# MotorDrive_REVB2.net
KiCad netlist of a schematic drawn in EAGLE
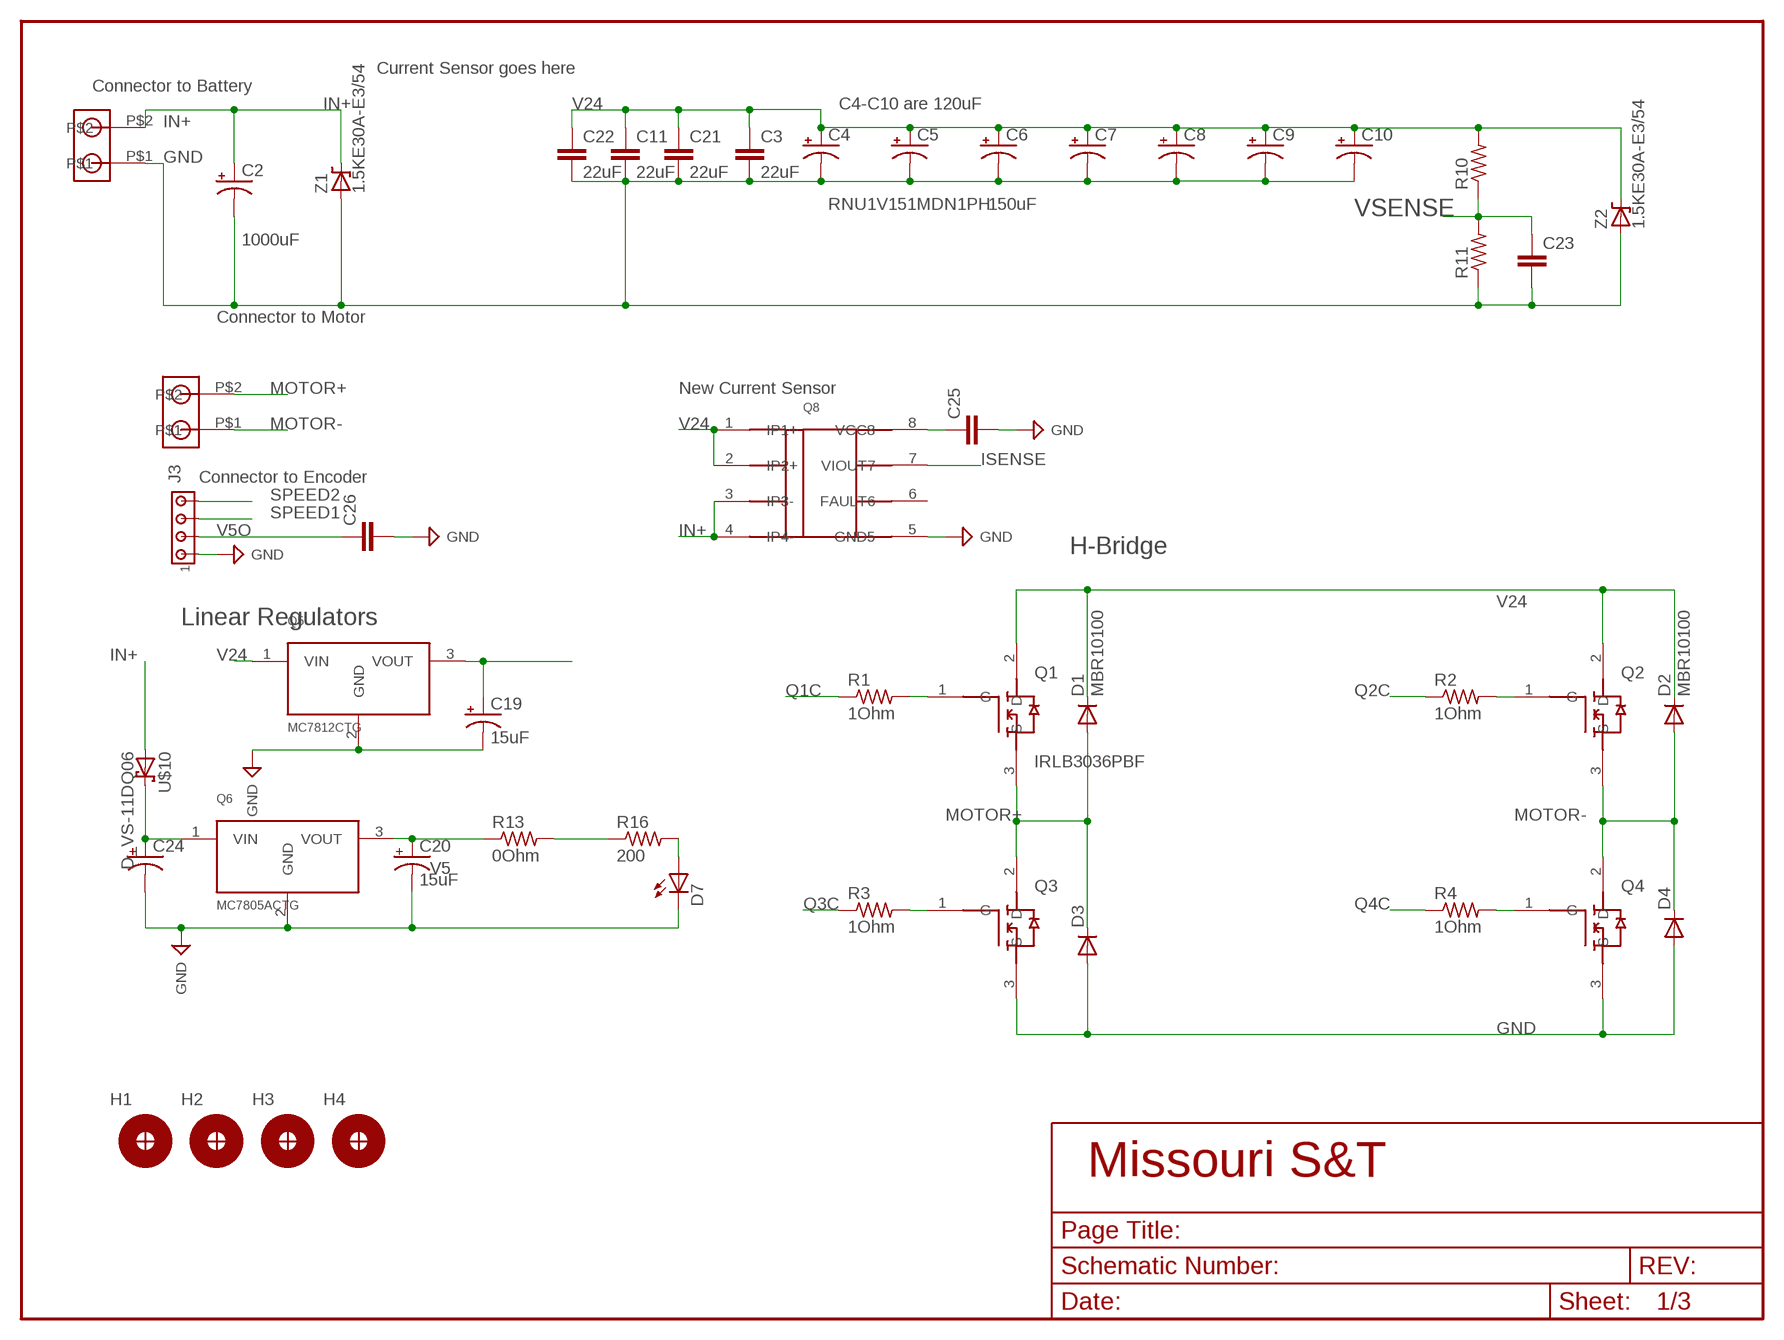
[diagram p0: schematic, sheet 1]
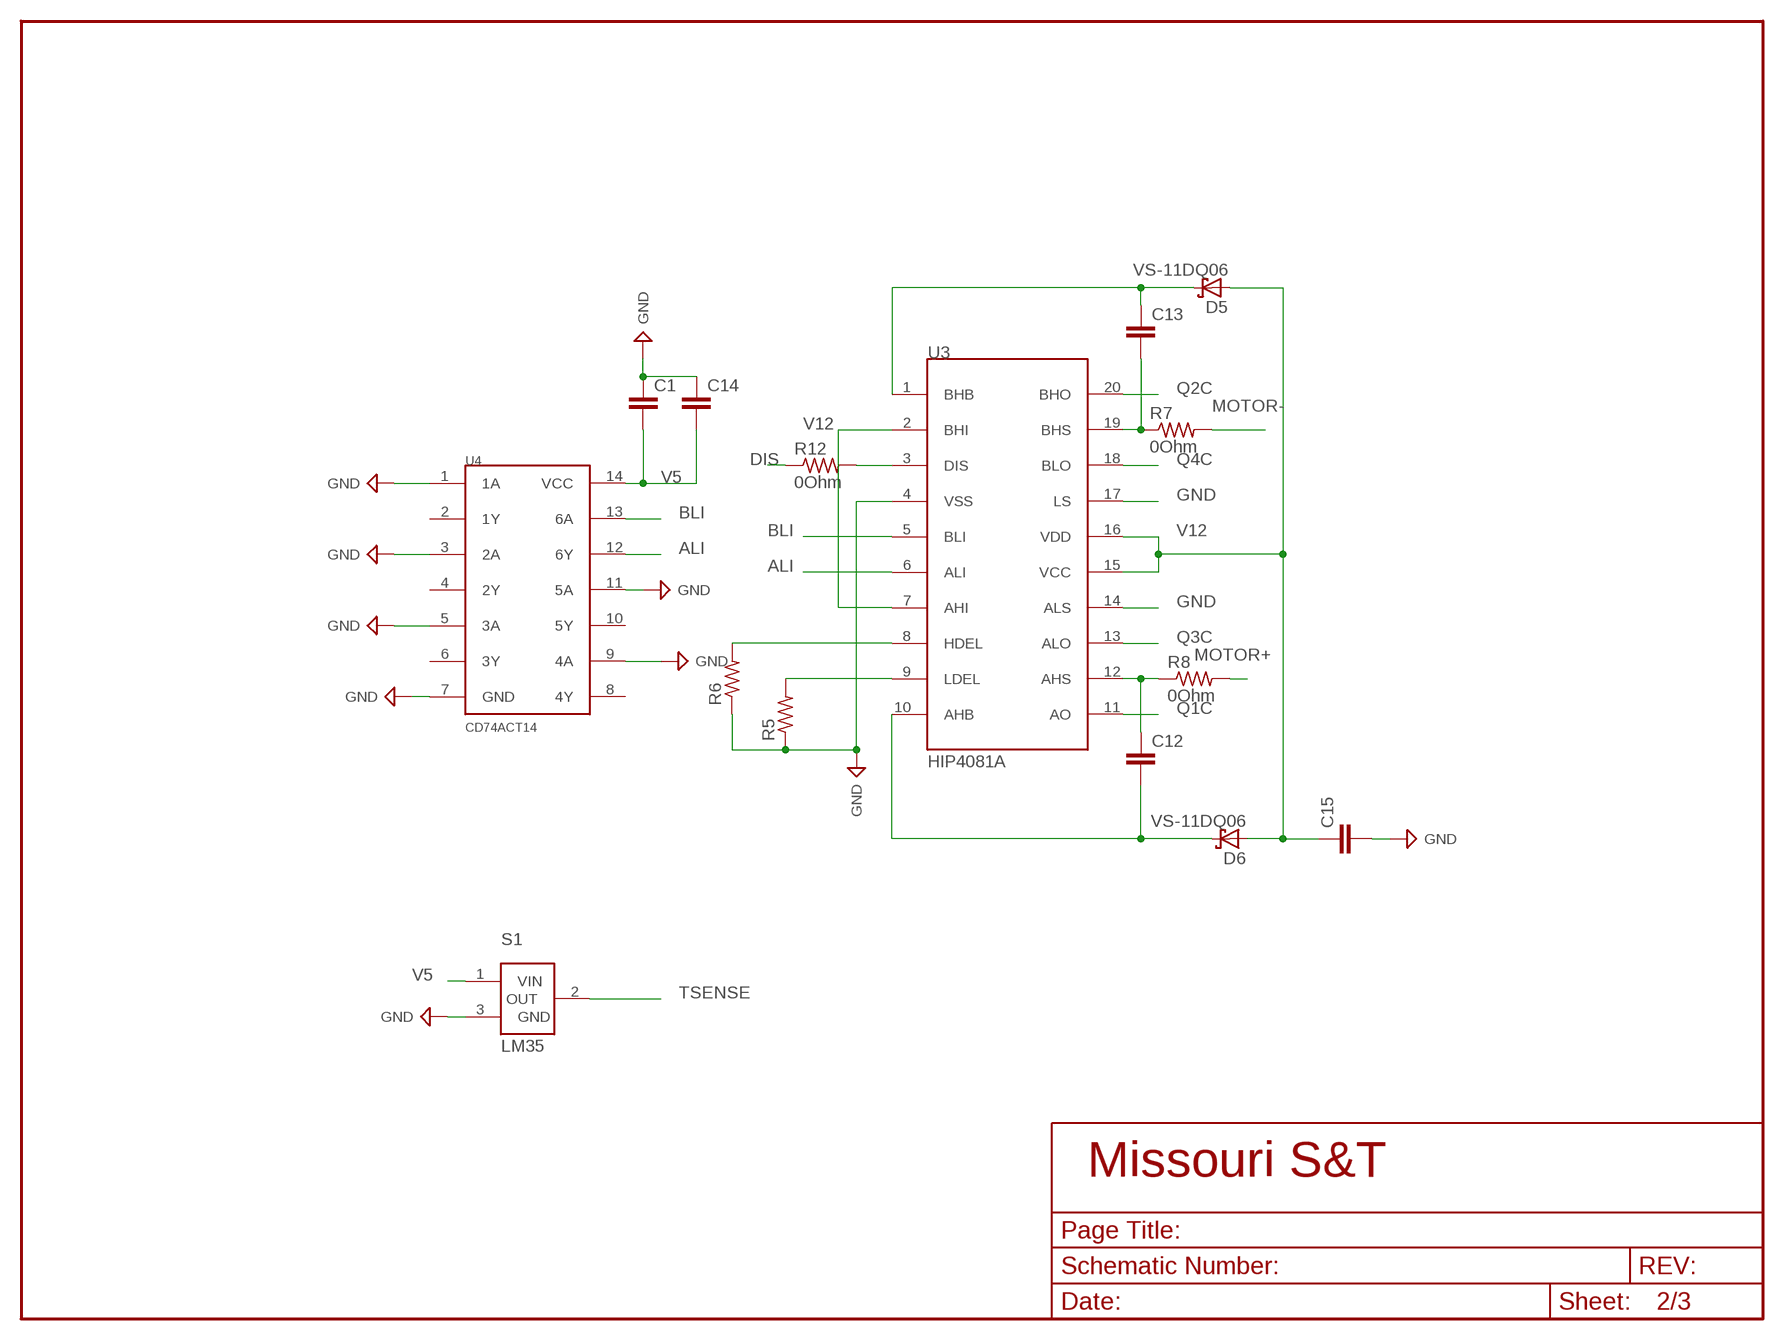
[diagram p1: schematic, sheet 2]
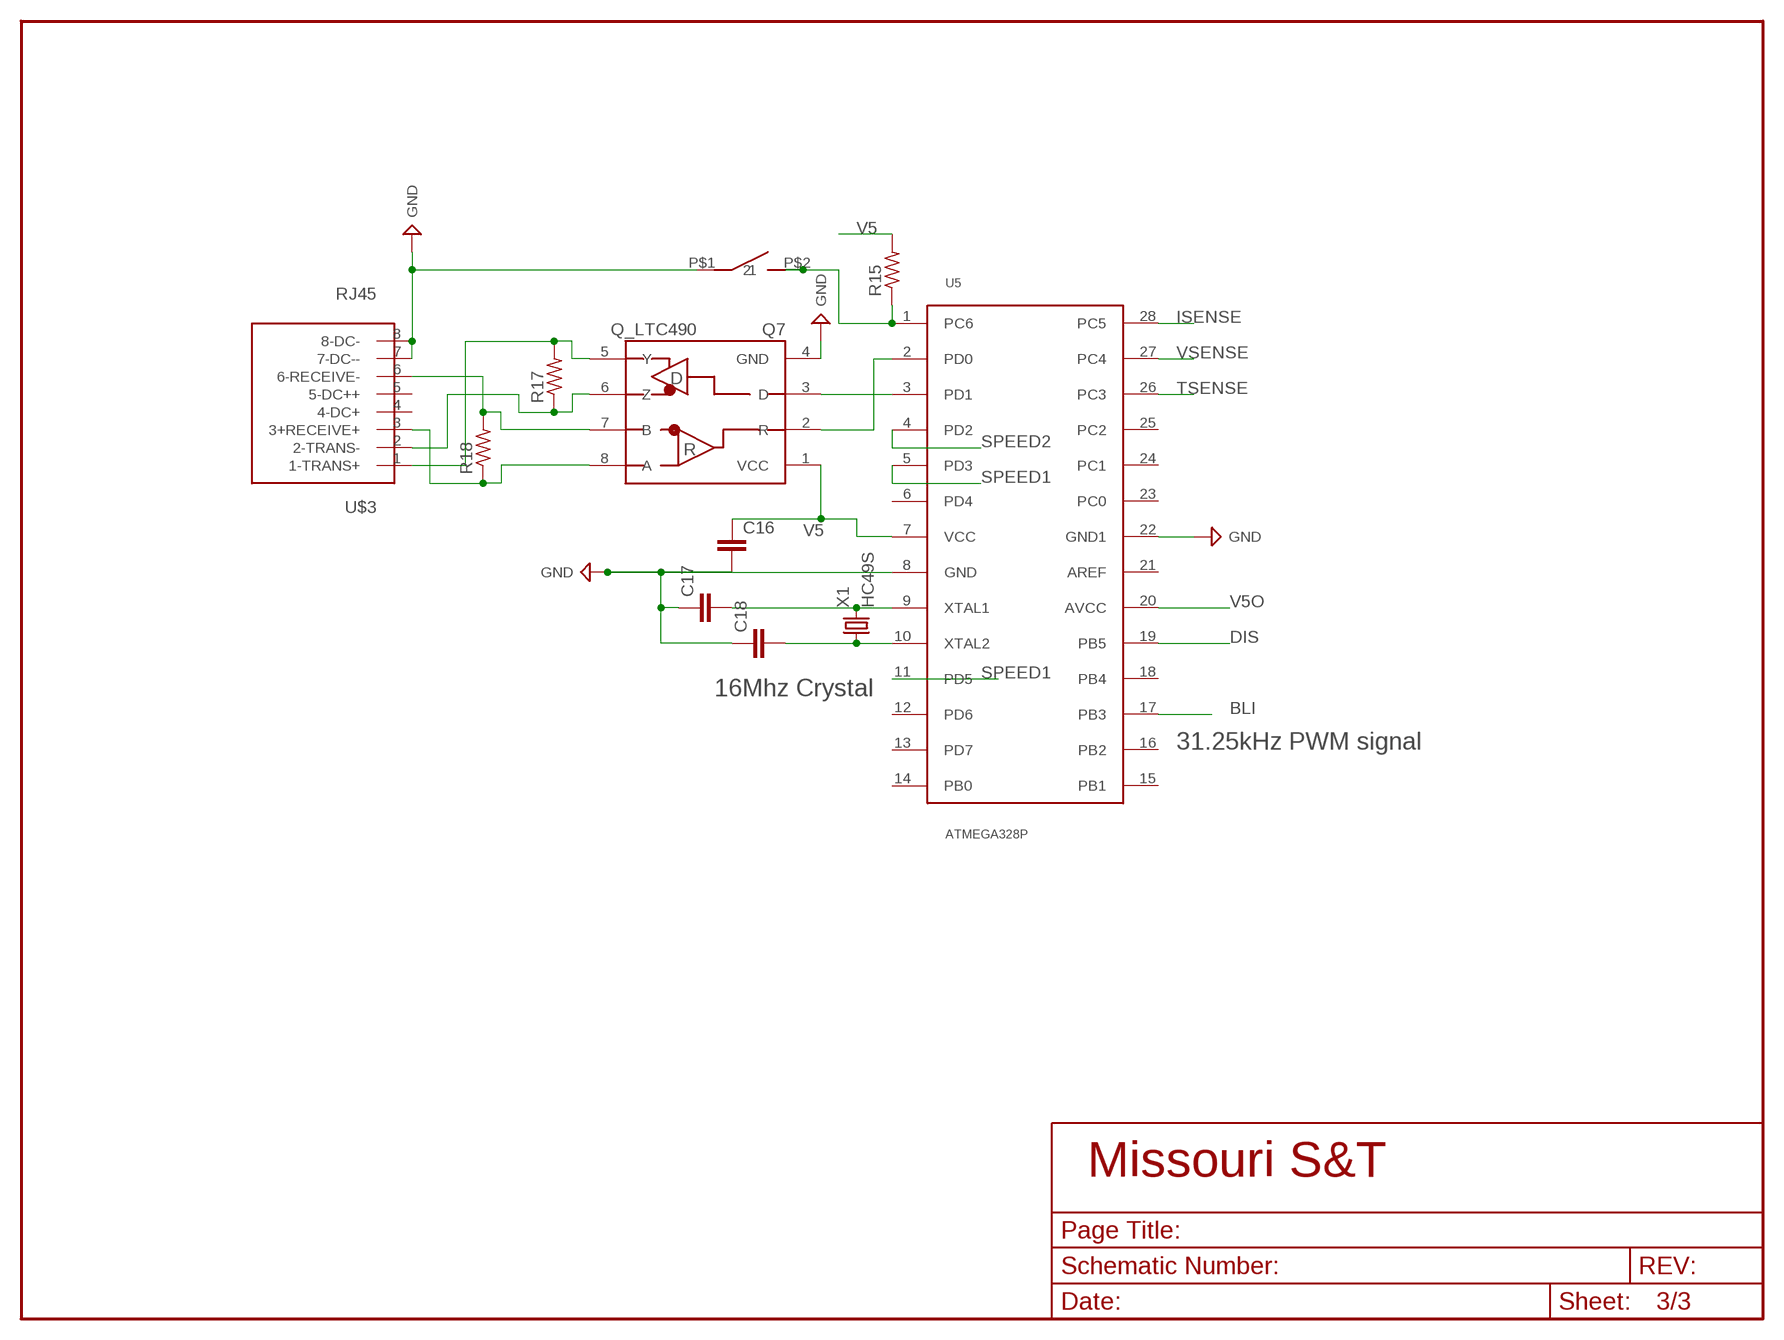
[diagram p2: schematic, sheet 3]

(export (version "E")
  (design (tool "Eeschema 10.0.6"))
  (components
    (comp (ref "C1")
      (value "C_CAP_1206")
      (footprint "eagle-import:C_1206")
      (libsource (lib "eagle-import") (part "C_CAP_1206"))
    )
    (comp (ref "C12")
      (value "C_CAP_1206")
      (footprint "eagle-import:C_1206")
      (libsource (lib "eagle-import") (part "C_CAP_1206"))
    )
    (comp (ref "C13")
      (value "C_CAP_1206")
      (footprint "eagle-import:C_1206")
      (libsource (lib "eagle-import") (part "C_CAP_1206"))
    )
    (comp (ref "C14")
      (value "C_CAP_1206")
      (footprint "eagle-import:C_1206")
      (libsource (lib "eagle-import") (part "C_CAP_1206"))
    )
    (comp (ref "C15")
      (value "C_CAP_1206")
      (footprint "eagle-import:C_1206")
      (libsource (lib "eagle-import") (part "C_CAP_1206"))
    )
    (comp (ref "D5")
      (value "VS-11DQ06")
      (footprint "eagle-import:DO-204AL")
      (libsource (lib "eagle-import") (part "D_VS-11DQ06"))
    )
    (comp (ref "D6")
      (value "VS-11DQ06")
      (footprint "eagle-import:DO-204AL")
      (libsource (lib "eagle-import") (part "D_VS-11DQ06"))
    )
    (comp (ref "R5")
      (value "R_RES_1206")
      (footprint "eagle-import:R_1206")
      (libsource (lib "eagle-import") (part "R_RES_1206"))
    )
    (comp (ref "R6")
      (value "R_RES_1206")
      (footprint "eagle-import:R_1206")
      (libsource (lib "eagle-import") (part "R_RES_1206"))
    )
    (comp (ref "R7")
      (value "0Ohm")
      (footprint "eagle-import:R_1_4W")
      (libsource (lib "eagle-import") (part "R_1/4W"))
    )
    (comp (ref "R8")
      (value "0Ohm")
      (footprint "eagle-import:R_1_4W")
      (libsource (lib "eagle-import") (part "R_1/4W"))
    )
    (comp (ref "R12")
      (value "0Ohm")
      (footprint "eagle-import:R_1_4W")
      (libsource (lib "eagle-import") (part "R_1/4W"))
    )
    (comp (ref "S1")
      (value "LM35")
      (footprint "eagle-import:TO-92-3")
      (libsource (lib "eagle-import") (part "Q_LM35TO-92"))
    )
    (comp (ref "U3")
      (value "HIP4081A")
      (footprint "eagle-import:DIP20")
      (libsource (lib "eagle-import") (part "Q_HIP4081A"))
    )
    (comp (ref "U4")
      (value "CD74ACT14")
      (footprint "eagle-import:DIP14")
      (libsource (lib "eagle-import") (part "Q_CD74ACT14"))
    )
    (comp (ref "C2")
      (value "1000uF")
      (footprint "eagle-import:C_10MM")
      (libsource (lib "eagle-import") (part "C_10MM"))
    )
    (comp (ref "C3")
      (value "22uF")
      (footprint "eagle-import:C_1206")
      (libsource (lib "eagle-import") (part "C_CAP_1206"))
    )
    (comp (ref "C4")
      (value "RNU1V151MDN1PH")
      (footprint "eagle-import:C_10MM")
      (libsource (lib "eagle-import") (part "C_10MM"))
    )
    (comp (ref "C5")
      (value "C_10MM")
      (footprint "eagle-import:C_10MM")
      (libsource (lib "eagle-import") (part "C_10MM"))
    )
    (comp (ref "C6")
      (value "C_10MM")
      (footprint "eagle-import:C_10MM")
      (libsource (lib "eagle-import") (part "C_10MM"))
    )
    (comp (ref "C7")
      (value "C_10MM")
      (footprint "eagle-import:C_10MM")
      (libsource (lib "eagle-import") (part "C_10MM"))
    )
    (comp (ref "C8")
      (value "C_10MM")
      (footprint "eagle-import:C_10MM")
      (libsource (lib "eagle-import") (part "C_10MM"))
    )
    (comp (ref "C9")
      (value "C_10MM")
      (footprint "eagle-import:C_10MM")
      (libsource (lib "eagle-import") (part "C_10MM"))
    )
    (comp (ref "C10")
      (value "150uF")
      (footprint "eagle-import:C_10MM")
      (libsource (lib "eagle-import") (part "C_10MM"))
    )
    (comp (ref "C11")
      (value "22uF")
      (footprint "eagle-import:C_1206")
      (libsource (lib "eagle-import") (part "C_CAP_1206"))
    )
    (comp (ref "C19")
      (value "15uF")
      (footprint "eagle-import:C_2MM")
      (libsource (lib "eagle-import") (part "C_GA1E150"))
    )
    (comp (ref "C20")
      (value "15uF")
      (footprint "eagle-import:C_8MM")
      (libsource (lib "eagle-import") (part "C_POL8MM"))
    )
    (comp (ref "C21")
      (value "22uF")
      (footprint "eagle-import:C_1206")
      (libsource (lib "eagle-import") (part "C_CAP_1206"))
    )
    (comp (ref "C22")
      (value "22uF")
      (footprint "eagle-import:C_1206")
      (libsource (lib "eagle-import") (part "C_CAP_1206"))
    )
    (comp (ref "C23")
      (value "C_CAP_1206")
      (footprint "eagle-import:C_1206")
      (libsource (lib "eagle-import") (part "C_CAP_1206"))
    )
    (comp (ref "C24")
      (value "C_POL_RAD_D8MM_LS200MIL_30MIL")
      (footprint "eagle-import:C_RAD_D8MM_LS200MIL_30MIL")
      (libsource (lib "eagle-import") (part "C_POL_RAD_D8MM_LS200MIL_30MIL"))
    )
    (comp (ref "C25")
      (value "C_CAP_1206")
      (footprint "eagle-import:C_1206")
      (libsource (lib "eagle-import") (part "C_CAP_1206"))
    )
    (comp (ref "C26")
      (value "C_CAP_1206")
      (footprint "eagle-import:C_1206")
      (libsource (lib "eagle-import") (part "C_CAP_1206"))
    )
    (comp (ref "D1")
      (value "MBR10100")
      (footprint "eagle-import:TO220AC")
      (libsource (lib "eagle-import") (part "D_FFPF10UA60ST"))
    )
    (comp (ref "D2")
      (value "MBR10100")
      (footprint "eagle-import:TO220AC")
      (libsource (lib "eagle-import") (part "D_FFPF10UA60ST"))
    )
    (comp (ref "D3")
      (value "D_FFPF10UA60ST")
      (footprint "eagle-import:TO220AC")
      (libsource (lib "eagle-import") (part "D_FFPF10UA60ST"))
    )
    (comp (ref "D4")
      (value "D_FFPF10UA60ST")
      (footprint "eagle-import:TO220AC")
      (libsource (lib "eagle-import") (part "D_FFPF10UA60ST"))
    )
    (comp (ref "D7")
      (value "D_LED_T1")
      (footprint "eagle-import:D_LED_T1")
      (libsource (lib "eagle-import") (part "D_LED_T1"))
    )
    (comp (ref "H1")
      (value "H_MNTHOLE_#4")
      (footprint "eagle-import:H_MNTHOLE_#4")
      (libsource (lib "eagle-import") (part "H_MNTHOLE_#4"))
    )
    (comp (ref "H2")
      (value "H_MNTHOLE_#4")
      (footprint "eagle-import:H_MNTHOLE_#4")
      (libsource (lib "eagle-import") (part "H_MNTHOLE_#4"))
    )
    (comp (ref "H3")
      (value "H_MNTHOLE_#4")
      (footprint "eagle-import:H_MNTHOLE_#4")
      (libsource (lib "eagle-import") (part "H_MNTHOLE_#4"))
    )
    (comp (ref "H4")
      (value "H_MNTHOLE_#4")
      (footprint "eagle-import:H_MNTHOLE_#4")
      (libsource (lib "eagle-import") (part "H_MNTHOLE_#4"))
    )
    (comp (ref "J1")
      (value "J_1546074-2")
      (footprint "eagle-import:THERM_BLOCK_2")
      (libsource (lib "eagle-import") (part "J_1546074-2"))
    )
    (comp (ref "J2")
      (value "J_1546074-2")
      (footprint "eagle-import:THERM_BLOCK_2")
      (libsource (lib "eagle-import") (part "J_1546074-2"))
    )
    (comp (ref "J3")
      (value "J_HDR1X4_MTA_100MIL")
      (footprint "eagle-import:J_MTA1X4_100MIL")
      (libsource (lib "eagle-import") (part "J_HDR1X4_MTA_100MIL"))
    )
    (comp (ref "Q1")
      (value "IRLB3036PBF")
      (footprint "eagle-import:TO220_6025DG")
      (libsource (lib "eagle-import") (part "Q_IRLB3036PBF"))
    )
    (comp (ref "Q2")
      (value "Q_IRLB3036PBF")
      (footprint "eagle-import:TO220_6025DG")
      (libsource (lib "eagle-import") (part "Q_IRLB3036PBF"))
    )
    (comp (ref "Q3")
      (value "Q_IRLB3036PBF")
      (footprint "eagle-import:TO220_6025DG")
      (libsource (lib "eagle-import") (part "Q_IRLB3036PBF"))
    )
    (comp (ref "Q4")
      (value "Q_IRLB3036PBF")
      (footprint "eagle-import:TO220_6025DG")
      (libsource (lib "eagle-import") (part "Q_IRLB3036PBF"))
    )
    (comp (ref "Q5")
      (value "MC7812CTG")
      (footprint "eagle-import:TO-220")
      (libsource (lib "eagle-import") (part "Q_LDO"))
    )
    (comp (ref "Q6")
      (value "MC7805ACTG")
      (footprint "eagle-import:TO-220")
      (libsource (lib "eagle-import") (part "Q_LDO"))
    )
    (comp (ref "Q8")
      (value "Q_SO8ACS711")
      (footprint "eagle-import:Q_SO8")
      (libsource (lib "eagle-import") (part "Q_SO8ACS711"))
    )
    (comp (ref "R1")
      (value "1Ohm")
      (footprint "eagle-import:R_1_4W")
      (libsource (lib "eagle-import") (part "R_1/4W"))
    )
    (comp (ref "R2")
      (value "1Ohm")
      (footprint "eagle-import:R_1_4W")
      (libsource (lib "eagle-import") (part "R_1/4W"))
    )
    (comp (ref "R3")
      (value "1Ohm")
      (footprint "eagle-import:R_1_4W")
      (libsource (lib "eagle-import") (part "R_1/4W"))
    )
    (comp (ref "R4")
      (value "1Ohm")
      (footprint "eagle-import:R_1_4W")
      (libsource (lib "eagle-import") (part "R_1/4W"))
    )
    (comp (ref "R10")
      (value "R_RES_1206")
      (footprint "eagle-import:R_1206")
      (libsource (lib "eagle-import") (part "R_RES_1206"))
    )
    (comp (ref "R11")
      (value "R_RES_1206")
      (footprint "eagle-import:R_1206")
      (libsource (lib "eagle-import") (part "R_RES_1206"))
    )
    (comp (ref "R13")
      (value "0Ohm")
      (footprint "eagle-import:R_1_4W")
      (libsource (lib "eagle-import") (part "R_1/4W"))
    )
    (comp (ref "R16")
      (value "200")
      (footprint "eagle-import:R_1206")
      (libsource (lib "eagle-import") (part "R_RES_1206"))
    )
    (comp (ref "U$10")
      (value "D_VS-11DQ06")
      (footprint "eagle-import:DO-204AL")
      (libsource (lib "eagle-import") (part "D_VS-11DQ06"))
    )
    (comp (ref "Z1")
      (value "1.5KE30A-E3/54")
      (footprint "eagle-import:DIODE_D3.5MM_LS15.24MM")
      (libsource (lib "eagle-import") (part "D_1.5KE480A_D3.5MM_LS15.24MM"))
    )
    (comp (ref "Z2")
      (value "1.5KE30A-E3/54")
      (footprint "eagle-import:DIODE_D3.5MM_LS15.24MM")
      (libsource (lib "eagle-import") (part "D_1.5KE480A_D3.5MM_LS15.24MM"))
    )
    (comp (ref "C16")
      (value "C_CAP_1206")
      (footprint "eagle-import:C_1206")
      (libsource (lib "eagle-import") (part "C_CAP_1206"))
    )
    (comp (ref "C17")
      (value "C_CAP_1206")
      (footprint "eagle-import:C_1206")
      (libsource (lib "eagle-import") (part "C_CAP_1206"))
    )
    (comp (ref "C18")
      (value "C_CAP_1206")
      (footprint "eagle-import:C_1206")
      (libsource (lib "eagle-import") (part "C_CAP_1206"))
    )
    (comp (ref "J8")
      (value "J_MC32857")
      (footprint "eagle-import:J_TOGGLE")
      (libsource (lib "eagle-import") (part "J_MC32857"))
    )
    (comp (ref "Q7")
      (value "Q_LTC490")
      (footprint "eagle-import:DIP8")
      (libsource (lib "eagle-import") (part "Q_LTC490"))
    )
    (comp (ref "R15")
      (value "R_RES_1206")
      (footprint "eagle-import:R_1206")
      (libsource (lib "eagle-import") (part "R_RES_1206"))
    )
    (comp (ref "R17")
      (value "R_RES_1206")
      (footprint "eagle-import:R_1206")
      (libsource (lib "eagle-import") (part "R_RES_1206"))
    )
    (comp (ref "R18")
      (value "R_RES_1206")
      (footprint "eagle-import:R_1206")
      (libsource (lib "eagle-import") (part "R_RES_1206"))
    )
    (comp (ref "U$3")
      (value "RJ45")
      (footprint "eagle-import:RJ45-CAT5E")
      (libsource (lib "eagle-import") (part "RJ45"))
    )
    (comp (ref "U5")
      (value "ATMEGA328P")
      (footprint "eagle-import:DIP28")
      (libsource (lib "eagle-import") (part "Q_ATMEGA328P"))
    )
    (comp (ref "X1")
      (value "HC49S")
      (footprint "eagle-import:HC-49")
      (libsource (lib "eagle-import") (part "X_HC49SCRYSTAL"))
    )
  )
  (nets
    (net (code "1") (name "ALI") (class "Default")
      (node (ref "U3") (pin "6") (pinfunction "ALI_6") (pintype "bidirectional"))
      (node (ref "U4") (pin "12") (pinfunction "6Y_12") (pintype "bidirectional"))
    )
    (net (code "2") (name "BLI") (class "Default")
      (node (ref "U3") (pin "5") (pinfunction "BLI_5") (pintype "bidirectional"))
      (node (ref "U4") (pin "13") (pinfunction "6A_13") (pintype "bidirectional"))
      (node (ref "U5") (pin "17") (pinfunction "PB3_17") (pintype "bidirectional"))
    )
    (net (code "3") (name "DIS") (class "Default")
      (node (ref "R12") (pin "1") (pinfunction "1_1") (pintype "passive"))
      (node (ref "U5") (pin "19") (pinfunction "PB5_19") (pintype "bidirectional"))
    )
    (net (code "4") (name "GND") (class "Default")
      (node (ref "C1") (pin "1") (pinfunction "1_1") (pintype "passive"))
      (node (ref "C10") (pin "P$2") (pinfunction "-_P$2") (pintype "passive"))
      (node (ref "C11") (pin "2") (pinfunction "2_2") (pintype "passive"))
      (node (ref "C14") (pin "1") (pinfunction "1_1") (pintype "passive"))
      (node (ref "C15") (pin "2") (pinfunction "2_2") (pintype "passive"))
      (node (ref "C16") (pin "2") (pinfunction "2_2") (pintype "passive"))
      (node (ref "C17") (pin "1") (pinfunction "1_1") (pintype "passive"))
      (node (ref "C18") (pin "1") (pinfunction "1_1") (pintype "passive"))
      (node (ref "C19") (pin "-") (pinfunction "-_-") (pintype "passive"))
      (node (ref "C2") (pin "P$2") (pinfunction "-_P$2") (pintype "passive"))
      (node (ref "C20") (pin "-") (pinfunction "-_-") (pintype "passive"))
      (node (ref "C21") (pin "2") (pinfunction "2_2") (pintype "passive"))
      (node (ref "C22") (pin "2") (pinfunction "2_2") (pintype "passive"))
      (node (ref "C23") (pin "2") (pinfunction "2_2") (pintype "passive"))
      (node (ref "C24") (pin "-") (pinfunction "-_-") (pintype "passive"))
      (node (ref "C25") (pin "2") (pinfunction "2_2") (pintype "passive"))
      (node (ref "C26") (pin "2") (pinfunction "2_2") (pintype "passive"))
      (node (ref "C3") (pin "2") (pinfunction "2_2") (pintype "passive"))
      (node (ref "C4") (pin "P$2") (pinfunction "-_P$2") (pintype "passive"))
      (node (ref "C5") (pin "P$2") (pinfunction "-_P$2") (pintype "passive"))
      (node (ref "C6") (pin "P$2") (pinfunction "-_P$2") (pintype "passive"))
      (node (ref "C7") (pin "P$2") (pinfunction "-_P$2") (pintype "passive"))
      (node (ref "C8") (pin "P$2") (pinfunction "-_P$2") (pintype "passive"))
      (node (ref "C9") (pin "P$2") (pinfunction "-_P$2") (pintype "passive"))
      (node (ref "D3") (pin "3") (pinfunction "A_3") (pintype "passive"))
      (node (ref "D4") (pin "3") (pinfunction "A_3") (pintype "passive"))
      (node (ref "D7") (pin "K") (pinfunction "C_K") (pintype "passive"))
      (node (ref "J2") (pin "P$1") (pinfunction "P$1_P$1") (pintype "bidirectional"))
      (node (ref "J3") (pin "1") (pinfunction "1_1") (pintype "passive"))
      (node (ref "J8") (pin "P$1") (pinfunction "1_P$1") (pintype "bidirectional"))
      (node (ref "Q3") (pin "3") (pinfunction "S_3") (pintype "bidirectional"))
      (node (ref "Q4") (pin "3") (pinfunction "S_3") (pintype "bidirectional"))
      (node (ref "Q5") (pin "2") (pinfunction "GND_2") (pintype "bidirectional"))
      (node (ref "Q6") (pin "2") (pinfunction "GND_2") (pintype "bidirectional"))
      (node (ref "Q7") (pin "4") (pinfunction "GND_4") (pintype "bidirectional"))
      (node (ref "Q8") (pin "5") (pinfunction "GND5_5") (pintype "bidirectional"))
      (node (ref "R11") (pin "1") (pinfunction "1_1") (pintype "passive"))
      (node (ref "R5") (pin "1") (pinfunction "1_1") (pintype "passive"))
      (node (ref "R6") (pin "1") (pinfunction "1_1") (pintype "passive"))
      (node (ref "S1") (pin "3") (pinfunction "GND_3") (pintype "bidirectional"))
      (node (ref "U$3") (pin "7") (pinfunction "7-DC--_7") (pintype "bidirectional"))
      (node (ref "U$3") (pin "8") (pinfunction "8-DC-_8") (pintype "bidirectional"))
      (node (ref "U3") (pin "14") (pinfunction "ALS_14") (pintype "bidirectional"))
      (node (ref "U3") (pin "17") (pinfunction "LS_17") (pintype "bidirectional"))
      (node (ref "U3") (pin "4") (pinfunction "VSS_4") (pintype "bidirectional"))
      (node (ref "U4") (pin "1") (pinfunction "1A_1") (pintype "bidirectional"))
      (node (ref "U4") (pin "11") (pinfunction "5A_11") (pintype "bidirectional"))
      (node (ref "U4") (pin "3") (pinfunction "2A_3") (pintype "bidirectional"))
      (node (ref "U4") (pin "5") (pinfunction "3A_5") (pintype "bidirectional"))
      (node (ref "U4") (pin "7") (pinfunction "GND_7") (pintype "bidirectional"))
      (node (ref "U4") (pin "9") (pinfunction "4A_9") (pintype "bidirectional"))
      (node (ref "U5") (pin "22") (pinfunction "GND1_22") (pintype "bidirectional"))
      (node (ref "U5") (pin "8") (pinfunction "GND_8") (pintype "bidirectional"))
      (node (ref "Z1") (pin "A") (pinfunction "A_A") (pintype "passive"))
      (node (ref "Z2") (pin "A") (pinfunction "A_A") (pintype "passive"))
    )
    (net (code "5") (name "IN+") (class "Default")
      (node (ref "C2") (pin "P$1") (pinfunction "+_P$1") (pintype "passive"))
      (node (ref "J2") (pin "P$2") (pinfunction "P$2_P$2") (pintype "bidirectional"))
      (node (ref "Q8") (pin "3") (pinfunction "IP3-_3") (pintype "bidirectional"))
      (node (ref "Q8") (pin "4") (pinfunction "IP4-_4") (pintype "bidirectional"))
      (node (ref "U$10") (pin "A") (pinfunction "A_A") (pintype "passive"))
      (node (ref "Z1") (pin "C") (pinfunction "K_C") (pintype "passive"))
    )
    (net (code "6") (name "ISENSE") (class "Default")
      (node (ref "Q8") (pin "7") (pinfunction "VIOUT7_7") (pintype "bidirectional"))
      (node (ref "U5") (pin "28") (pinfunction "PC5_28") (pintype "bidirectional"))
    )
    (net (code "7") (name "MOTOR+") (class "Default")
      (node (ref "D1") (pin "3") (pinfunction "A_3") (pintype "passive"))
      (node (ref "D3") (pin "1") (pinfunction "C_1") (pintype "passive"))
      (node (ref "J1") (pin "P$2") (pinfunction "P$2_P$2") (pintype "bidirectional"))
      (node (ref "Q1") (pin "3") (pinfunction "S_3") (pintype "bidirectional"))
      (node (ref "Q3") (pin "2") (pinfunction "D_2") (pintype "bidirectional"))
      (node (ref "R8") (pin "2") (pinfunction "2_2") (pintype "passive"))
    )
    (net (code "8") (name "MOTOR-") (class "Default")
      (node (ref "D2") (pin "3") (pinfunction "A_3") (pintype "passive"))
      (node (ref "D4") (pin "1") (pinfunction "C_1") (pintype "passive"))
      (node (ref "J1") (pin "P$1") (pinfunction "P$1_P$1") (pintype "bidirectional"))
      (node (ref "Q2") (pin "3") (pinfunction "S_3") (pintype "bidirectional"))
      (node (ref "Q4") (pin "2") (pinfunction "D_2") (pintype "bidirectional"))
      (node (ref "R7") (pin "2") (pinfunction "2_2") (pintype "passive"))
    )
    (net (code "9") (name "Net-(D7-PadA)") (class "Default")
      (node (ref "D7") (pin "A") (pinfunction "A_A") (pintype "passive"))
      (node (ref "R16") (pin "2") (pinfunction "2_2") (pintype "passive"))
    )
    (net (code "10") (name "Net-(J8-2)") (class "Default")
      (node (ref "J8") (pin "P$2") (pinfunction "2_P$2") (pintype "bidirectional"))
      (node (ref "R15") (pin "1") (pinfunction "1_1") (pintype "passive"))
      (node (ref "U5") (pin "1") (pinfunction "PC6_1") (pintype "bidirectional"))
    )
    (net (code "11") (name "Net-(Q1-G)") (class "Default")
      (node (ref "Q1") (pin "1") (pinfunction "G_1") (pintype "bidirectional"))
      (node (ref "R1") (pin "2") (pinfunction "2_2") (pintype "passive"))
    )
    (net (code "12") (name "Net-(Q2-G)") (class "Default")
      (node (ref "Q2") (pin "1") (pinfunction "G_1") (pintype "bidirectional"))
      (node (ref "R2") (pin "2") (pinfunction "2_2") (pintype "passive"))
    )
    (net (code "13") (name "Net-(Q3-G)") (class "Default")
      (node (ref "Q3") (pin "1") (pinfunction "G_1") (pintype "bidirectional"))
      (node (ref "R3") (pin "2") (pinfunction "2_2") (pintype "passive"))
    )
    (net (code "14") (name "Net-(Q4-G)") (class "Default")
      (node (ref "Q4") (pin "1") (pinfunction "G_1") (pintype "bidirectional"))
      (node (ref "R4") (pin "2") (pinfunction "2_2") (pintype "passive"))
    )
    (net (code "15") (name "Net-(Q6-VIN)") (class "Default")
      (node (ref "C24") (pin "+") (pinfunction "+_+") (pintype "passive"))
      (node (ref "Q6") (pin "1") (pinfunction "VIN_1") (pintype "bidirectional"))
      (node (ref "U$10") (pin "C") (pinfunction "C_C") (pintype "passive"))
    )
    (net (code "16") (name "Net-(Q7-A)") (class "Default")
      (node (ref "Q7") (pin "8") (pinfunction "A_8") (pintype "bidirectional"))
      (node (ref "R18") (pin "1") (pinfunction "1_1") (pintype "passive"))
      (node (ref "U$3") (pin "3") (pinfunction "3+RECEIVE+_3") (pintype "bidirectional"))
    )
    (net (code "17") (name "Net-(Q7-B)") (class "Default")
      (node (ref "Q7") (pin "7") (pinfunction "B_7") (pintype "bidirectional"))
      (node (ref "R18") (pin "2") (pinfunction "2_2") (pintype "passive"))
      (node (ref "U$3") (pin "6") (pinfunction "6-RECEIVE-_6") (pintype "bidirectional"))
    )
    (net (code "18") (name "Net-(Q7-D)") (class "Default")
      (node (ref "Q7") (pin "3") (pinfunction "D_3") (pintype "bidirectional"))
      (node (ref "U5") (pin "3") (pinfunction "PD1_3") (pintype "bidirectional"))
    )
    (net (code "19") (name "Net-(Q7-R)") (class "Default")
      (node (ref "Q7") (pin "2") (pinfunction "R_2") (pintype "bidirectional"))
      (node (ref "U5") (pin "2") (pinfunction "PD0_2") (pintype "bidirectional"))
    )
    (net (code "20") (name "Net-(Q7-Y)") (class "Default")
      (node (ref "Q7") (pin "5") (pinfunction "Y_5") (pintype "bidirectional"))
      (node (ref "R17") (pin "2") (pinfunction "2_2") (pintype "passive"))
      (node (ref "U$3") (pin "1") (pinfunction "1-TRANS+_1") (pintype "bidirectional"))
    )
    (net (code "21") (name "Net-(Q7-Z)") (class "Default")
      (node (ref "Q7") (pin "6") (pinfunction "Z_6") (pintype "bidirectional"))
      (node (ref "R17") (pin "1") (pinfunction "1_1") (pintype "passive"))
      (node (ref "U$3") (pin "2") (pinfunction "2-TRANS-_2") (pintype "bidirectional"))
    )
    (net (code "22") (name "Net-(U3-AHB)") (class "Default")
      (node (ref "C12") (pin "2") (pinfunction "2_2") (pintype "passive"))
      (node (ref "D6") (pin "C") (pinfunction "C_C") (pintype "passive"))
      (node (ref "U3") (pin "10") (pinfunction "AHB_10") (pintype "bidirectional"))
    )
    (net (code "23") (name "Net-(U3-AHS)") (class "Default")
      (node (ref "C12") (pin "1") (pinfunction "1_1") (pintype "passive"))
      (node (ref "R8") (pin "1") (pinfunction "1_1") (pintype "passive"))
      (node (ref "U3") (pin "12") (pinfunction "AHS_12") (pintype "bidirectional"))
    )
    (net (code "24") (name "Net-(U3-BHB)") (class "Default")
      (node (ref "C13") (pin "1") (pinfunction "1_1") (pintype "passive"))
      (node (ref "D5") (pin "C") (pinfunction "C_C") (pintype "passive"))
      (node (ref "U3") (pin "1") (pinfunction "BHB_1") (pintype "bidirectional"))
    )
    (net (code "25") (name "Net-(U3-BHS)") (class "Default")
      (node (ref "C13") (pin "2") (pinfunction "2_2") (pintype "passive"))
      (node (ref "R7") (pin "1") (pinfunction "1_1") (pintype "passive"))
      (node (ref "U3") (pin "19") (pinfunction "BHS_19") (pintype "bidirectional"))
    )
    (net (code "26") (name "Net-(U3-DIS)") (class "Default")
      (node (ref "R12") (pin "2") (pinfunction "2_2") (pintype "passive"))
      (node (ref "U3") (pin "3") (pinfunction "DIS_3") (pintype "bidirectional"))
    )
    (net (code "27") (name "Net-(U3-HDEL)") (class "Default")
      (node (ref "R6") (pin "2") (pinfunction "2_2") (pintype "passive"))
      (node (ref "U3") (pin "8") (pinfunction "HDEL_8") (pintype "bidirectional"))
    )
    (net (code "28") (name "Net-(U3-LDEL)") (class "Default")
      (node (ref "R5") (pin "2") (pinfunction "2_2") (pintype "passive"))
      (node (ref "U3") (pin "9") (pinfunction "LDEL_9") (pintype "bidirectional"))
    )
    (net (code "29") (name "Net-(U5-XTAL1)") (class "Default")
      (node (ref "C17") (pin "2") (pinfunction "2_2") (pintype "passive"))
      (node (ref "U5") (pin "9") (pinfunction "XTAL1_9") (pintype "bidirectional"))
      (node (ref "X1") (pin "P$2") (pinfunction "2_P$2") (pintype "passive"))
    )
    (net (code "30") (name "Net-(U5-XTAL2)") (class "Default")
      (node (ref "C18") (pin "2") (pinfunction "2_2") (pintype "passive"))
      (node (ref "U5") (pin "10") (pinfunction "XTAL2_10") (pintype "bidirectional"))
      (node (ref "X1") (pin "P$1") (pinfunction "1_P$1") (pintype "passive"))
    )
    (net (code "31") (name "Q1C") (class "Default")
      (node (ref "R1") (pin "1") (pinfunction "1_1") (pintype "passive"))
      (node (ref "U3") (pin "11") (pinfunction "AO_11") (pintype "bidirectional"))
    )
    (net (code "32") (name "Q2C") (class "Default")
      (node (ref "R2") (pin "1") (pinfunction "1_1") (pintype "passive"))
      (node (ref "U3") (pin "20") (pinfunction "BHO_20") (pintype "bidirectional"))
    )
    (net (code "33") (name "Q3C") (class "Default")
      (node (ref "R3") (pin "1") (pinfunction "1_1") (pintype "passive"))
      (node (ref "U3") (pin "13") (pinfunction "ALO_13") (pintype "bidirectional"))
    )
    (net (code "34") (name "Q4C") (class "Default")
      (node (ref "R4") (pin "1") (pinfunction "1_1") (pintype "passive"))
      (node (ref "U3") (pin "18") (pinfunction "BLO_18") (pintype "bidirectional"))
    )
    (net (code "35") (name "SPEED1") (class "Default")
      (node (ref "J3") (pin "3") (pinfunction "3_3") (pintype "passive"))
      (node (ref "U5") (pin "11") (pinfunction "PD5_11") (pintype "bidirectional"))
      (node (ref "U5") (pin "5") (pinfunction "PD3_5") (pintype "bidirectional"))
    )
    (net (code "36") (name "SPEED2") (class "Default")
      (node (ref "J3") (pin "4") (pinfunction "4_4") (pintype "passive"))
      (node (ref "U5") (pin "4") (pinfunction "PD2_4") (pintype "bidirectional"))
    )
    (net (code "37") (name "TSENSE") (class "Default")
      (node (ref "S1") (pin "2") (pinfunction "OUT_2") (pintype "bidirectional"))
      (node (ref "U5") (pin "26") (pinfunction "PC3_26") (pintype "bidirectional"))
    )
    (net (code "38") (name "V5") (class "Default")
      (node (ref "C1") (pin "2") (pinfunction "2_2") (pintype "passive"))
      (node (ref "C14") (pin "2") (pinfunction "2_2") (pintype "passive"))
      (node (ref "C16") (pin "1") (pinfunction "1_1") (pintype "passive"))
      (node (ref "C20") (pin "+") (pinfunction "+_+") (pintype "passive"))
      (node (ref "C25") (pin "1") (pinfunction "1_1") (pintype "passive"))
      (node (ref "Q6") (pin "3") (pinfunction "VOUT_3") (pintype "bidirectional"))
      (node (ref "Q7") (pin "1") (pinfunction "VCC_1") (pintype "bidirectional"))
      (node (ref "Q8") (pin "8") (pinfunction "VCC8_8") (pintype "bidirectional"))
      (node (ref "R13") (pin "1") (pinfunction "1_1") (pintype "passive"))
      (node (ref "R15") (pin "2") (pinfunction "2_2") (pintype "passive"))
      (node (ref "S1") (pin "1") (pinfunction "VIN_1") (pintype "bidirectional"))
      (node (ref "U4") (pin "14") (pinfunction "VCC_14") (pintype "bidirectional"))
      (node (ref "U5") (pin "7") (pinfunction "VCC_7") (pintype "bidirectional"))
    )
    (net (code "39") (name "V5O") (class "Default")
      (node (ref "C26") (pin "1") (pinfunction "1_1") (pintype "passive"))
      (node (ref "J3") (pin "2") (pinfunction "2_2") (pintype "passive"))
      (node (ref "R13") (pin "2") (pinfunction "2_2") (pintype "passive"))
      (node (ref "R16") (pin "1") (pinfunction "1_1") (pintype "passive"))
      (node (ref "U5") (pin "20") (pinfunction "AVCC_20") (pintype "bidirectional"))
    )
    (net (code "40") (name "V12") (class "Default")
      (node (ref "C15") (pin "1") (pinfunction "1_1") (pintype "passive"))
      (node (ref "C19") (pin "+") (pinfunction "+_+") (pintype "passive"))
      (node (ref "D5") (pin "A") (pinfunction "A_A") (pintype "passive"))
      (node (ref "D6") (pin "A") (pinfunction "A_A") (pintype "passive"))
      (node (ref "Q5") (pin "3") (pinfunction "VOUT_3") (pintype "bidirectional"))
      (node (ref "U3") (pin "15") (pinfunction "VCC_15") (pintype "bidirectional"))
      (node (ref "U3") (pin "16") (pinfunction "VDD_16") (pintype "bidirectional"))
      (node (ref "U3") (pin "2") (pinfunction "BHI_2") (pintype "bidirectional"))
      (node (ref "U3") (pin "7") (pinfunction "AHI_7") (pintype "bidirectional"))
    )
    (net (code "41") (name "V24") (class "Default")
      (node (ref "C10") (pin "P$1") (pinfunction "+_P$1") (pintype "passive"))
      (node (ref "C11") (pin "1") (pinfunction "1_1") (pintype "passive"))
      (node (ref "C21") (pin "1") (pinfunction "1_1") (pintype "passive"))
      (node (ref "C22") (pin "1") (pinfunction "1_1") (pintype "passive"))
      (node (ref "C3") (pin "1") (pinfunction "1_1") (pintype "passive"))
      (node (ref "C4") (pin "P$1") (pinfunction "+_P$1") (pintype "passive"))
      (node (ref "C5") (pin "P$1") (pinfunction "+_P$1") (pintype "passive"))
      (node (ref "C6") (pin "P$1") (pinfunction "+_P$1") (pintype "passive"))
      (node (ref "C7") (pin "P$1") (pinfunction "+_P$1") (pintype "passive"))
      (node (ref "C8") (pin "P$1") (pinfunction "+_P$1") (pintype "passive"))
      (node (ref "C9") (pin "P$1") (pinfunction "+_P$1") (pintype "passive"))
      (node (ref "D1") (pin "1") (pinfunction "C_1") (pintype "passive"))
      (node (ref "D2") (pin "1") (pinfunction "C_1") (pintype "passive"))
      (node (ref "Q1") (pin "2") (pinfunction "D_2") (pintype "bidirectional"))
      (node (ref "Q2") (pin "2") (pinfunction "D_2") (pintype "bidirectional"))
      (node (ref "Q5") (pin "1") (pinfunction "VIN_1") (pintype "bidirectional"))
      (node (ref "Q8") (pin "1") (pinfunction "IP1+_1") (pintype "bidirectional"))
      (node (ref "Q8") (pin "2") (pinfunction "IP2+_2") (pintype "bidirectional"))
      (node (ref "R10") (pin "2") (pinfunction "2_2") (pintype "passive"))
      (node (ref "Z2") (pin "C") (pinfunction "K_C") (pintype "passive"))
    )
    (net (code "42") (name "VSENSE") (class "Default")
      (node (ref "C23") (pin "1") (pinfunction "1_1") (pintype "passive"))
      (node (ref "R10") (pin "1") (pinfunction "1_1") (pintype "passive"))
      (node (ref "R11") (pin "2") (pinfunction "2_2") (pintype "passive"))
      (node (ref "U5") (pin "27") (pinfunction "PC4_27") (pintype "bidirectional"))
    )
    (net (code "43") (name "unconnected-(H1-Pad1)") (class "Default")
      (node (ref "H1") (pin "1") (pinfunction "1_1") (pintype "passive"))
    )
    (net (code "44") (name "unconnected-(H2-Pad1)") (class "Default")
      (node (ref "H2") (pin "1") (pinfunction "1_1") (pintype "passive"))
    )
    (net (code "45") (name "unconnected-(H3-Pad1)") (class "Default")
      (node (ref "H3") (pin "1") (pinfunction "1_1") (pintype "passive"))
    )
    (net (code "46") (name "unconnected-(H4-Pad1)") (class "Default")
      (node (ref "H4") (pin "1") (pinfunction "1_1") (pintype "passive"))
    )
    (net (code "47") (name "unconnected-(Q8-FAULT6-Pad6)") (class "Default")
      (node (ref "Q8") (pin "6") (pinfunction "FAULT6_6") (pintype "bidirectional"))
    )
    (net (code "48") (name "unconnected-(U$3-4-DC+-Pad4)") (class "Default")
      (node (ref "U$3") (pin "4") (pinfunction "4-DC+_4") (pintype "bidirectional"))
    )
    (net (code "49") (name "unconnected-(U$3-5-DC++-Pad5)") (class "Default")
      (node (ref "U$3") (pin "5") (pinfunction "5-DC++_5") (pintype "bidirectional"))
    )
    (net (code "50") (name "unconnected-(U4-1Y-Pad2)") (class "Default")
      (node (ref "U4") (pin "2") (pinfunction "1Y_2") (pintype "bidirectional"))
    )
    (net (code "51") (name "unconnected-(U4-2Y-Pad4)") (class "Default")
      (node (ref "U4") (pin "4") (pinfunction "2Y_4") (pintype "bidirectional"))
    )
    (net (code "52") (name "unconnected-(U4-3Y-Pad6)") (class "Default")
      (node (ref "U4") (pin "6") (pinfunction "3Y_6") (pintype "bidirectional"))
    )
    (net (code "53") (name "unconnected-(U4-4Y-Pad8)") (class "Default")
      (node (ref "U4") (pin "8") (pinfunction "4Y_8") (pintype "bidirectional"))
    )
    (net (code "54") (name "unconnected-(U4-5Y-Pad10)") (class "Default")
      (node (ref "U4") (pin "10") (pinfunction "5Y_10") (pintype "bidirectional"))
    )
    (net (code "55") (name "unconnected-(U5-AREF-Pad21)") (class "Default")
      (node (ref "U5") (pin "21") (pinfunction "AREF_21") (pintype "bidirectional"))
    )
    (net (code "56") (name "unconnected-(U5-PB0-Pad14)") (class "Default")
      (node (ref "U5") (pin "14") (pinfunction "PB0_14") (pintype "bidirectional"))
    )
    (net (code "57") (name "unconnected-(U5-PB1-Pad15)") (class "Default")
      (node (ref "U5") (pin "15") (pinfunction "PB1_15") (pintype "bidirectional"))
    )
    (net (code "58") (name "unconnected-(U5-PB2-Pad16)") (class "Default")
      (node (ref "U5") (pin "16") (pinfunction "PB2_16") (pintype "bidirectional"))
    )
    (net (code "59") (name "unconnected-(U5-PB4-Pad18)") (class "Default")
      (node (ref "U5") (pin "18") (pinfunction "PB4_18") (pintype "bidirectional"))
    )
    (net (code "60") (name "unconnected-(U5-PC0-Pad23)") (class "Default")
      (node (ref "U5") (pin "23") (pinfunction "PC0_23") (pintype "bidirectional"))
    )
    (net (code "61") (name "unconnected-(U5-PC1-Pad24)") (class "Default")
      (node (ref "U5") (pin "24") (pinfunction "PC1_24") (pintype "bidirectional"))
    )
    (net (code "62") (name "unconnected-(U5-PC2-Pad25)") (class "Default")
      (node (ref "U5") (pin "25") (pinfunction "PC2_25") (pintype "bidirectional"))
    )
    (net (code "63") (name "unconnected-(U5-PD4-Pad6)") (class "Default")
      (node (ref "U5") (pin "6") (pinfunction "PD4_6") (pintype "bidirectional"))
    )
    (net (code "64") (name "unconnected-(U5-PD6-Pad12)") (class "Default")
      (node (ref "U5") (pin "12") (pinfunction "PD6_12") (pintype "bidirectional"))
    )
    (net (code "65") (name "unconnected-(U5-PD7-Pad13)") (class "Default")
      (node (ref "U5") (pin "13") (pinfunction "PD7_13") (pintype "bidirectional"))
    )
  )
)
